# 6_DIG.net
KiCad netlist of a schematic drawn in Altium Designer
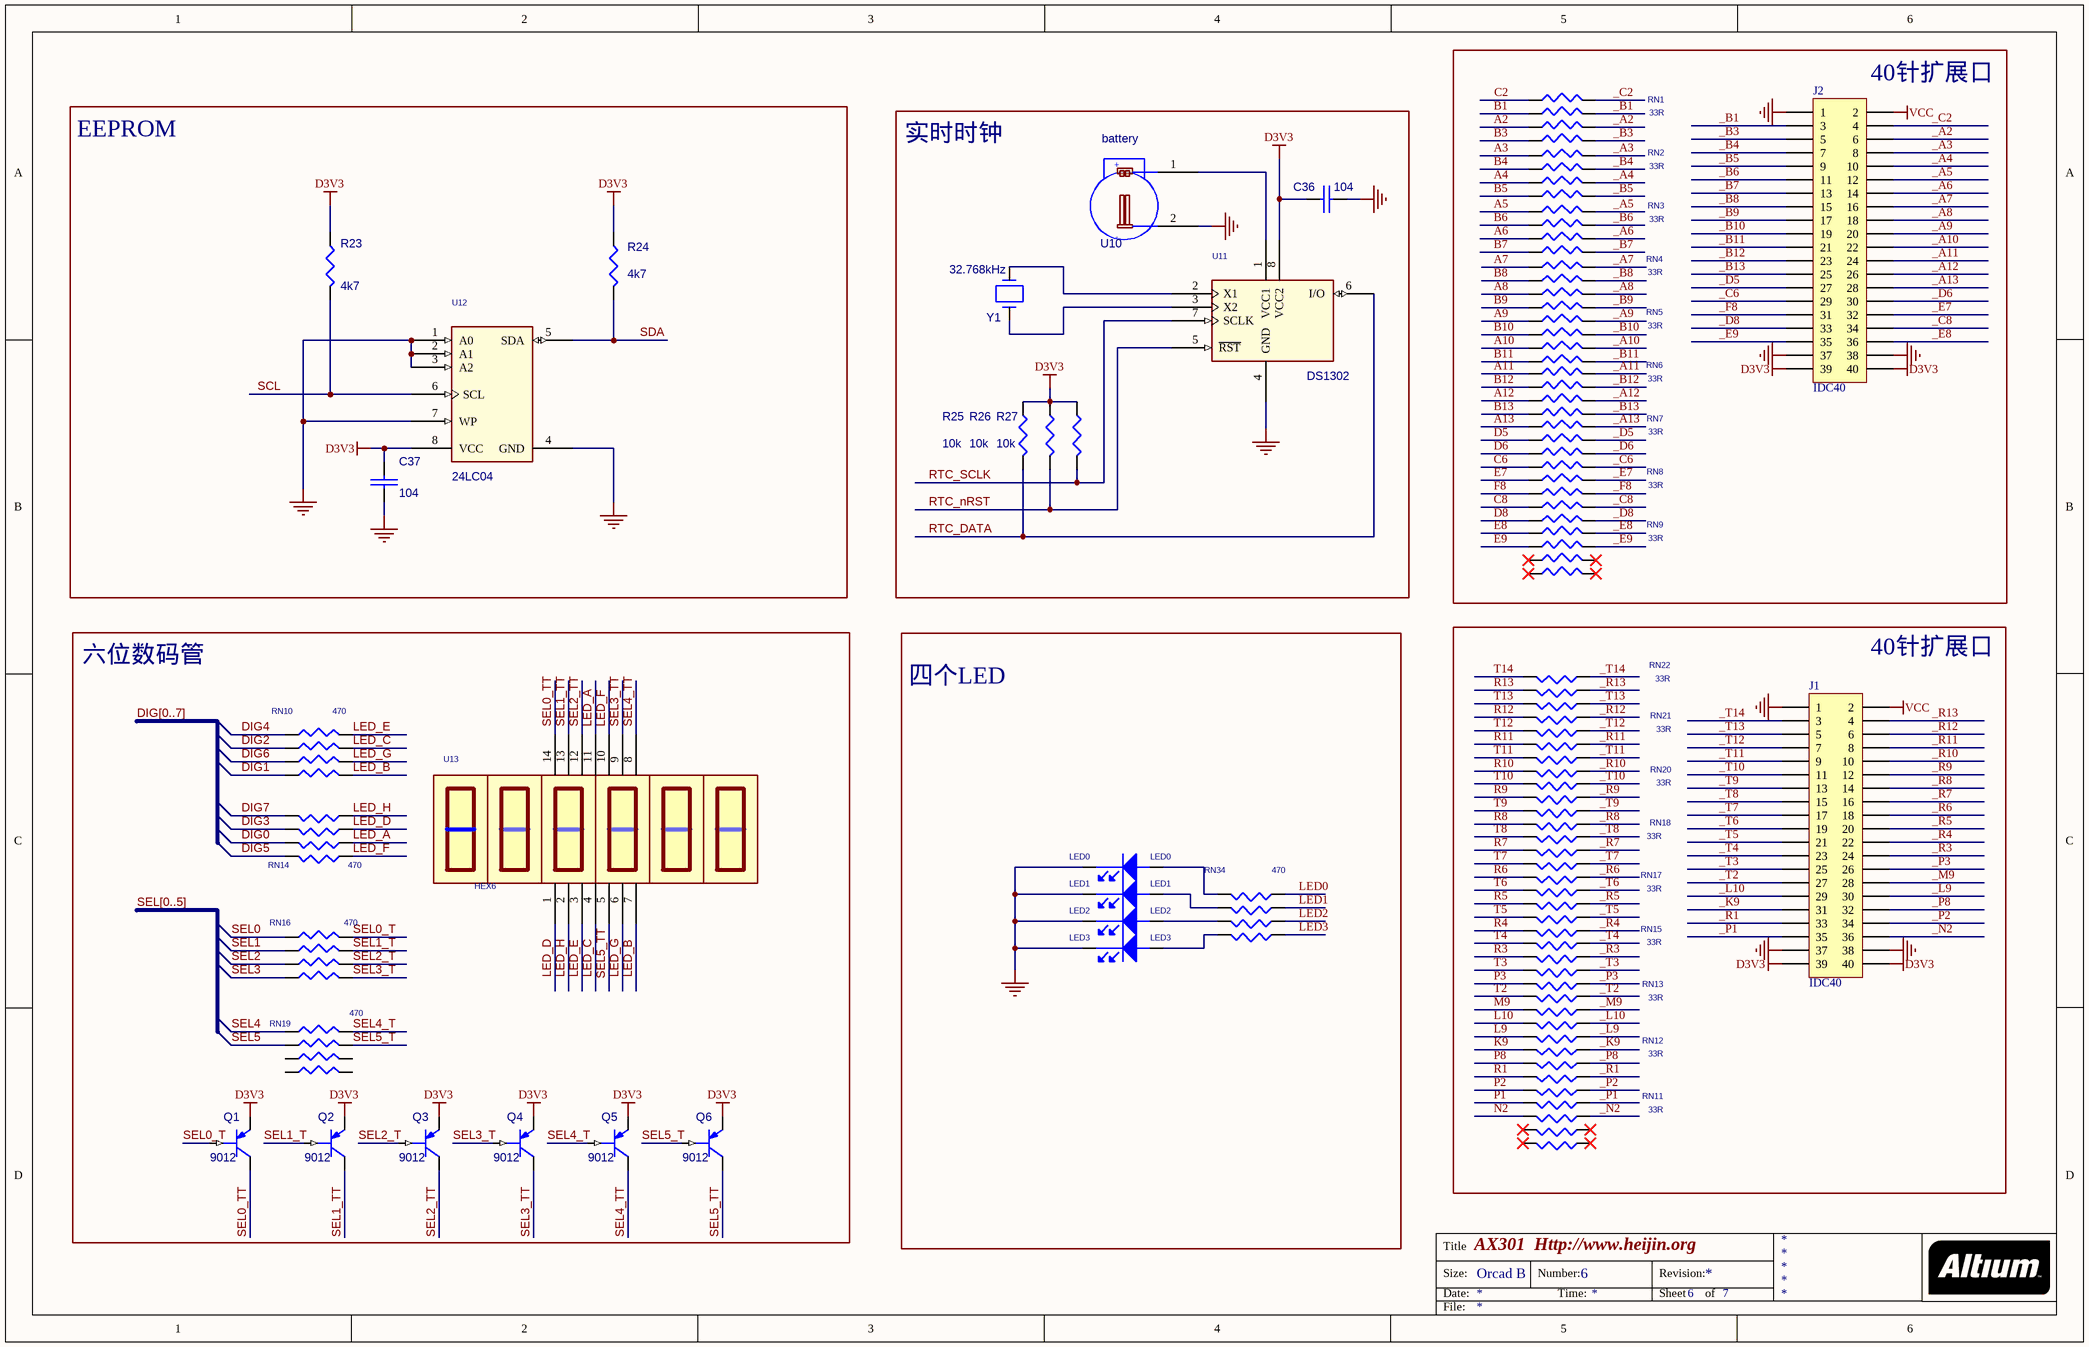
[diagram p0: 6_DIG.SchDoc]

(export (version "E")
  (design (tool "Eeschema 10.0.6"))
  (components
    (comp (ref "C36") (value "104") (footprint "0402") (libsource (lib "*") (part "C_Dup3")))
    (comp (ref "C37") (value "104") (footprint "0402") (libsource (lib "*") (part "C_Dup4")))
    (comp (ref "J1")
      (value "IDC40")
      (footprint "IDC-40J")
      (description "Header, 20-Pin, Dual row")
      (fields (field (name "PUBLISHER") "Altium Limited"))
      (libsource (lib "Miscellaneous Connectors") (part "MHDR2X20"))
    )
    (comp (ref "J2")
      (value "IDC40")
      (footprint "IDC-40J")
      (description "Header, 20-Pin, Dual row")
      (fields (field (name "PUBLISHER") "Altium Limited"))
      (libsource (lib "Miscellaneous Connectors") (part "MHDR2X20"))
    )
    (comp (ref "LED0") (value "LED0") (footprint "LEDSO") (libsource (lib "*") (part "LED_Dup1")))
    (comp (ref "LED1") (value "LED1") (footprint "LEDso") (libsource (lib "*") (part "LED_Dup1")))
    (comp (ref "LED2") (value "LED2") (footprint "LEDSO") (libsource (lib "*") (part "LED_Dup1")))
    (comp (ref "LED3") (value "LED3") (footprint "LEDSO") (libsource (lib "*") (part "LED_Dup1")))
    (comp (ref "Q1") (value "9012") (footprint "SOT23") (libsource (lib "*") (part "PNP")))
    (comp (ref "Q2") (value "9012") (footprint "SOT23") (libsource (lib "*") (part "PNP")))
    (comp (ref "Q3") (value "9012") (footprint "SOT23") (libsource (lib "*") (part "PNP")))
    (comp (ref "Q4") (value "9012") (footprint "SOT23") (libsource (lib "*") (part "PNP")))
    (comp (ref "Q5") (value "9012") (footprint "SOT23") (libsource (lib "*") (part "PNP")))
    (comp (ref "Q6") (value "9012") (footprint "SOT23") (libsource (lib "*") (part "PNP")))
    (comp (ref "R23") (value "4k7") (footprint "0603") (libsource (lib "*") (part "R_Dup6")))
    (comp (ref "R24") (value "4k7") (footprint "0603") (libsource (lib "*") (part "R_Dup6")))
    (comp (ref "R25") (value "10k") (footprint "0603") (libsource (lib "*") (part "R_Dup5")))
    (comp (ref "R26") (value "10k") (footprint "0603") (libsource (lib "*") (part "R_Dup5")))
    (comp (ref "R27") (value "10k") (footprint "0603") (libsource (lib "*") (part "R_Dup5")))
    (comp (ref "RN1") (value "33R") (footprint "RN-8P") (libsource (lib "*") (part "RN_Dup1")))
    (comp (ref "RN2") (value "33R") (footprint "RN-8P") (libsource (lib "*") (part "RN_Dup1")))
    (comp (ref "RN3") (value "33R") (footprint "RN-8P") (libsource (lib "*") (part "RN_Dup1")))
    (comp (ref "RN4") (value "33R") (footprint "RN-8P") (libsource (lib "*") (part "RN_Dup1")))
    (comp (ref "RN5") (value "33R") (footprint "RN-8P") (libsource (lib "*") (part "RN_Dup1")))
    (comp (ref "RN6") (value "33R") (footprint "RN-8P") (libsource (lib "*") (part "RN_Dup1")))
    (comp (ref "RN7") (value "33R") (footprint "RN-8P") (libsource (lib "*") (part "RN_Dup1")))
    (comp (ref "RN8") (value "33R") (footprint "RN-8P") (libsource (lib "*") (part "RN_Dup1")))
    (comp (ref "RN9") (value "33R") (footprint "RN-8P") (libsource (lib "*") (part "RN_Dup1")))
    (comp (ref "RN10") (value "470") (footprint "RN-8P") (libsource (lib "*") (part "RN")))
    (comp (ref "RN11") (value "33R") (footprint "RN-8P") (libsource (lib "*") (part "RN_Dup1")))
    (comp (ref "RN12") (value "33R") (footprint "RN-8P") (libsource (lib "*") (part "RN_Dup1")))
    (comp (ref "RN13") (value "33R") (footprint "RN-8P") (libsource (lib "*") (part "RN_Dup1")))
    (comp (ref "RN14") (value "470") (footprint "RN-8P") (libsource (lib "*") (part "RN")))
    (comp (ref "RN15") (value "33R") (footprint "RN-8P") (libsource (lib "*") (part "RN_Dup1")))
    (comp (ref "RN16") (value "470") (footprint "RN-8P") (libsource (lib "*") (part "RN")))
    (comp (ref "RN17") (value "33R") (footprint "RN-8P") (libsource (lib "*") (part "RN_Dup1")))
    (comp (ref "RN18") (value "33R") (footprint "RN-8P") (libsource (lib "*") (part "RN_Dup1")))
    (comp (ref "RN19") (value "470") (footprint "RN-8P") (libsource (lib "*") (part "RN")))
    (comp (ref "RN20") (value "33R") (footprint "RN-8P") (libsource (lib "*") (part "RN_Dup1")))
    (comp (ref "RN21") (value "33R") (footprint "RN-8P") (libsource (lib "*") (part "RN_Dup1")))
    (comp (ref "RN22") (value "33R") (footprint "RN-8P") (libsource (lib "*") (part "RN_Dup1")))
    (comp (ref "RN34") (value "470") (footprint "RN-8P") (libsource (lib "*") (part "RN")))
    (comp (ref "U10") (value "battery") (footprint "BATSO") (libsource (lib "*") (part "battery")))
    (comp (ref "U11")
      (value "DS1302")
      (fields (field (name "PART NUMBER") "TMP-13") (field (name "ICA_PARTNUM") "$$2098133$$DS1302S"))
      (libsource (lib "*") (part "DS1302_8SO"))
    )
    (comp (ref "U12") (value "24LC04") (libsource (lib "*") (part "24LC04B_0")))
    (comp (ref "U13") (value "HEX6") (libsource (lib "*") (part "HEX6")))
    (comp (ref "Y1") (value "32.768kHz") (libsource (lib "*") (part "ZTA")))
  )
  (nets
    (net (code "1") (name "/A2") (class "Default")
      (node (ref "RN1") (pin "3") (pinfunction "3_3") (pintype "passive"))
    )
    (net (code "2") (name "/A3") (class "Default")
      (node (ref "RN2") (pin "1") (pinfunction "1_1") (pintype "passive"))
    )
    (net (code "3") (name "/A4") (class "Default")
      (node (ref "RN2") (pin "3") (pinfunction "3_3") (pintype "passive"))
    )
    (net (code "4") (name "/A5") (class "Default")
      (node (ref "RN3") (pin "1") (pinfunction "1_1") (pintype "passive"))
    )
    (net (code "5") (name "/A6") (class "Default")
      (node (ref "RN3") (pin "3") (pinfunction "3_3") (pintype "passive"))
    )
    (net (code "6") (name "/A7") (class "Default")
      (node (ref "RN4") (pin "1") (pinfunction "1_1") (pintype "passive"))
    )
    (net (code "7") (name "/A8") (class "Default")
      (node (ref "RN4") (pin "3") (pinfunction "3_3") (pintype "passive"))
    )
    (net (code "8") (name "/A9") (class "Default")
      (node (ref "RN5") (pin "1") (pinfunction "1_1") (pintype "passive"))
    )
    (net (code "9") (name "/A10") (class "Default")
      (node (ref "RN5") (pin "3") (pinfunction "3_3") (pintype "passive"))
    )
    (net (code "10") (name "/A11") (class "Default")
      (node (ref "RN6") (pin "1") (pinfunction "1_1") (pintype "passive"))
    )
    (net (code "11") (name "/A12") (class "Default")
      (node (ref "RN6") (pin "3") (pinfunction "3_3") (pintype "passive"))
    )
    (net (code "12") (name "/A13") (class "Default")
      (node (ref "RN7") (pin "1") (pinfunction "1_1") (pintype "passive"))
    )
    (net (code "13") (name "/B1") (class "Default")
      (node (ref "RN1") (pin "2") (pinfunction "2_2") (pintype "passive"))
    )
    (net (code "14") (name "/B3") (class "Default")
      (node (ref "RN1") (pin "4") (pinfunction "4_4") (pintype "passive"))
    )
    (net (code "15") (name "/B4") (class "Default")
      (node (ref "RN2") (pin "2") (pinfunction "2_2") (pintype "passive"))
    )
    (net (code "16") (name "/B5") (class "Default")
      (node (ref "RN2") (pin "4") (pinfunction "4_4") (pintype "passive"))
    )
    (net (code "17") (name "/B6") (class "Default")
      (node (ref "RN3") (pin "2") (pinfunction "2_2") (pintype "passive"))
    )
    (net (code "18") (name "/B7") (class "Default")
      (node (ref "RN3") (pin "4") (pinfunction "4_4") (pintype "passive"))
    )
    (net (code "19") (name "/B8") (class "Default")
      (node (ref "RN4") (pin "2") (pinfunction "2_2") (pintype "passive"))
    )
    (net (code "20") (name "/B9") (class "Default")
      (node (ref "RN4") (pin "4") (pinfunction "4_4") (pintype "passive"))
    )
    (net (code "21") (name "/B10") (class "Default")
      (node (ref "RN5") (pin "2") (pinfunction "2_2") (pintype "passive"))
    )
    (net (code "22") (name "/B11") (class "Default")
      (node (ref "RN5") (pin "4") (pinfunction "4_4") (pintype "passive"))
    )
    (net (code "23") (name "/B12") (class "Default")
      (node (ref "RN6") (pin "2") (pinfunction "2_2") (pintype "passive"))
    )
    (net (code "24") (name "/B13") (class "Default")
      (node (ref "RN6") (pin "4") (pinfunction "4_4") (pintype "passive"))
    )
    (net (code "25") (name "/C2") (class "Default")
      (node (ref "RN1") (pin "1") (pinfunction "1_1") (pintype "passive"))
    )
    (net (code "26") (name "/C6") (class "Default")
      (node (ref "RN7") (pin "4") (pinfunction "4_4") (pintype "passive"))
    )
    (net (code "27") (name "/C8") (class "Default")
      (node (ref "RN8") (pin "3") (pinfunction "3_3") (pintype "passive"))
    )
    (net (code "28") (name "/D5") (class "Default")
      (node (ref "RN7") (pin "2") (pinfunction "2_2") (pintype "passive"))
    )
    (net (code "29") (name "/D6") (class "Default")
      (node (ref "RN7") (pin "3") (pinfunction "3_3") (pintype "passive"))
    )
    (net (code "30") (name "/D8") (class "Default")
      (node (ref "RN8") (pin "4") (pinfunction "4_4") (pintype "passive"))
    )
    (net (code "31") (name "/DIG0") (class "Default")
      (node (ref "RN14") (pin "7") (pinfunction "7_7") (pintype "passive"))
    )
    (net (code "32") (name "/DIG1") (class "Default")
      (node (ref "RN10") (pin "5") (pinfunction "5_5") (pintype "passive"))
    )
    (net (code "33") (name "/DIG2") (class "Default")
      (node (ref "RN10") (pin "7") (pinfunction "7_7") (pintype "passive"))
    )
    (net (code "34") (name "/DIG3") (class "Default")
      (node (ref "RN14") (pin "6") (pinfunction "6_6") (pintype "passive"))
    )
    (net (code "35") (name "/DIG4") (class "Default")
      (node (ref "RN10") (pin "8") (pinfunction "8_8") (pintype "passive"))
    )
    (net (code "36") (name "/DIG5") (class "Default")
      (node (ref "RN14") (pin "8") (pinfunction "8_8") (pintype "passive"))
    )
    (net (code "37") (name "/DIG6") (class "Default")
      (node (ref "RN10") (pin "6") (pinfunction "6_6") (pintype "passive"))
    )
    (net (code "38") (name "/DIG7") (class "Default")
      (node (ref "RN14") (pin "5") (pinfunction "5_5") (pintype "passive"))
    )
    (net (code "40") (name "/E7") (class "Default")
      (node (ref "RN8") (pin "1") (pinfunction "1_1") (pintype "passive"))
    )
    (net (code "41") (name "/E8") (class "Default")
      (node (ref "RN9") (pin "1") (pinfunction "1_1") (pintype "passive"))
    )
    (net (code "42") (name "/E9") (class "Default")
      (node (ref "RN9") (pin "2") (pinfunction "2_2") (pintype "passive"))
    )
    (net (code "43") (name "/F8") (class "Default")
      (node (ref "RN8") (pin "2") (pinfunction "2_2") (pintype "passive"))
    )
    (net (code "44") (name "/K9") (class "Default")
      (node (ref "RN12") (pin "5") (pinfunction "5_5") (pintype "passive"))
    )
    (net (code "45") (name "/L9") (class "Default")
      (node (ref "RN13") (pin "8") (pinfunction "8_8") (pintype "passive"))
    )
    (net (code "46") (name "/L10") (class "Default")
      (node (ref "RN13") (pin "7") (pinfunction "7_7") (pintype "passive"))
    )
    (net (code "47") (name "/LED0") (class "Default")
      (node (ref "RN34") (pin "4") (pinfunction "4_4") (pintype "passive"))
    )
    (net (code "48") (name "/LED1") (class "Default")
      (node (ref "RN34") (pin "3") (pinfunction "3_3") (pintype "passive"))
    )
    (net (code "49") (name "/LED2") (class "Default")
      (node (ref "RN34") (pin "2") (pinfunction "2_2") (pintype "passive"))
    )
    (net (code "50") (name "/LED3") (class "Default")
      (node (ref "RN34") (pin "1") (pinfunction "1_1") (pintype "passive"))
    )
    (net (code "51") (name "/LED_A") (class "Default")
      (node (ref "RN14") (pin "2") (pinfunction "2_2") (pintype "passive"))
      (node (ref "U13") (pin "11") (pinfunction "11_11") (pintype "passive"))
    )
    (net (code "52") (name "/LED_B") (class "Default")
      (node (ref "RN10") (pin "4") (pinfunction "4_4") (pintype "passive"))
      (node (ref "U13") (pin "7") (pinfunction "7_7") (pintype "passive"))
    )
    (net (code "53") (name "/LED_C") (class "Default")
      (node (ref "RN10") (pin "2") (pinfunction "2_2") (pintype "passive"))
      (node (ref "U13") (pin "4") (pinfunction "4_4") (pintype "passive"))
    )
    (net (code "54") (name "/LED_D") (class "Default")
      (node (ref "RN14") (pin "3") (pinfunction "3_3") (pintype "passive"))
      (node (ref "U13") (pin "1") (pinfunction "1_1") (pintype "passive"))
    )
    (net (code "55") (name "/LED_E") (class "Default")
      (node (ref "RN10") (pin "1") (pinfunction "1_1") (pintype "passive"))
      (node (ref "U13") (pin "3") (pinfunction "3_3") (pintype "passive"))
    )
    (net (code "56") (name "/LED_F") (class "Default")
      (node (ref "RN14") (pin "1") (pinfunction "1_1") (pintype "passive"))
      (node (ref "U13") (pin "10") (pinfunction "10_10") (pintype "passive"))
    )
    (net (code "57") (name "/LED_G") (class "Default")
      (node (ref "RN10") (pin "3") (pinfunction "3_3") (pintype "passive"))
      (node (ref "U13") (pin "6") (pinfunction "6_6") (pintype "passive"))
    )
    (net (code "58") (name "/LED_H") (class "Default")
      (node (ref "RN14") (pin "4") (pinfunction "4_4") (pintype "passive"))
      (node (ref "U13") (pin "2") (pinfunction "2_2") (pintype "passive"))
    )
    (net (code "59") (name "/M9") (class "Default")
      (node (ref "RN13") (pin "6") (pinfunction "6_6") (pintype "passive"))
    )
    (net (code "60") (name "/N2") (class "Default")
      (node (ref "RN11") (pin "6") (pinfunction "6_6") (pintype "passive"))
    )
    (net (code "61") (name "/P1") (class "Default")
      (node (ref "RN11") (pin "5") (pinfunction "5_5") (pintype "passive"))
    )
    (net (code "62") (name "/P2") (class "Default")
      (node (ref "RN12") (pin "8") (pinfunction "8_8") (pintype "passive"))
    )
    (net (code "63") (name "/P3") (class "Default")
      (node (ref "RN15") (pin "8") (pinfunction "8_8") (pintype "passive"))
    )
    (net (code "64") (name "/P8") (class "Default")
      (node (ref "RN12") (pin "6") (pinfunction "6_6") (pintype "passive"))
    )
    (net (code "65") (name "/R1") (class "Default")
      (node (ref "RN12") (pin "7") (pinfunction "7_7") (pintype "passive"))
    )
    (net (code "66") (name "/R3") (class "Default")
      (node (ref "RN15") (pin "6") (pinfunction "6_6") (pintype "passive"))
    )
    (net (code "67") (name "/R4") (class "Default")
      (node (ref "RN17") (pin "8") (pinfunction "8_8") (pintype "passive"))
    )
    (net (code "68") (name "/R5") (class "Default")
      (node (ref "RN17") (pin "6") (pinfunction "6_6") (pintype "passive"))
    )
    (net (code "69") (name "/R6") (class "Default")
      (node (ref "RN18") (pin "8") (pinfunction "8_8") (pintype "passive"))
    )
    (net (code "70") (name "/R7") (class "Default")
      (node (ref "RN18") (pin "6") (pinfunction "6_6") (pintype "passive"))
    )
    (net (code "71") (name "/R8") (class "Default")
      (node (ref "RN20") (pin "8") (pinfunction "8_8") (pintype "passive"))
    )
    (net (code "72") (name "/R9") (class "Default")
      (node (ref "RN20") (pin "6") (pinfunction "6_6") (pintype "passive"))
    )
    (net (code "73") (name "/R10") (class "Default")
      (node (ref "RN21") (pin "8") (pinfunction "8_8") (pintype "passive"))
    )
    (net (code "74") (name "/R11") (class "Default")
      (node (ref "RN21") (pin "6") (pinfunction "6_6") (pintype "passive"))
    )
    (net (code "75") (name "/R12") (class "Default")
      (node (ref "RN22") (pin "8") (pinfunction "8_8") (pintype "passive"))
    )
    (net (code "76") (name "/R13") (class "Default")
      (node (ref "RN22") (pin "6") (pinfunction "6_6") (pintype "passive"))
    )
    (net (code "77") (name "/RTC_DATA") (class "Default")
      (node (ref "R25") (pin "2") (pinfunction "2_2") (pintype "passive"))
      (node (ref "U11") (pin "6") (pinfunction "I/O_6") (pintype "bidirectional"))
    )
    (net (code "78") (name "/RTC_SCLK") (class "Default")
      (node (ref "R27") (pin "2") (pinfunction "2_2") (pintype "passive"))
      (node (ref "U11") (pin "7") (pinfunction "SCLK_7") (pintype "input"))
    )
    (net (code "79") (name "/RTC_nRST") (class "Default")
      (node (ref "R26") (pin "2") (pinfunction "2_2") (pintype "passive"))
      (node (ref "U11") (pin "5") (pinfunction "~{RST}_5") (pintype "input"))
    )
    (net (code "80") (name "/SCL") (class "Default")
      (node (ref "R23") (pin "2") (pinfunction "2_2") (pintype "passive"))
      (node (ref "U12") (pin "6") (pinfunction "SCL_6") (pintype "input"))
    )
    (net (code "81") (name "/SDA") (class "Default")
      (node (ref "R24") (pin "2") (pinfunction "2_2") (pintype "passive"))
      (node (ref "U12") (pin "5") (pinfunction "SDA_5") (pintype "bidirectional"))
    )
    (net (code "82") (name "/SEL0") (class "Default")
      (node (ref "RN16") (pin "8") (pinfunction "8_8") (pintype "passive"))
    )
    (net (code "83") (name "/SEL0_T") (class "Default")
      (node (ref "Q1") (pin "1") (pinfunction "BASE_1") (pintype "input"))
      (node (ref "RN16") (pin "1") (pinfunction "1_1") (pintype "passive"))
    )
    (net (code "84") (name "/SEL0_TT") (class "Default")
      (node (ref "Q1") (pin "3") (pinfunction "COLLECTOR_3") (pintype "passive"))
      (node (ref "U13") (pin "14") (pinfunction "14_14") (pintype "passive"))
    )
    (net (code "85") (name "/SEL1") (class "Default")
      (node (ref "RN16") (pin "7") (pinfunction "7_7") (pintype "passive"))
    )
    (net (code "86") (name "/SEL1_T") (class "Default")
      (node (ref "Q2") (pin "1") (pinfunction "BASE_1") (pintype "input"))
      (node (ref "RN16") (pin "2") (pinfunction "2_2") (pintype "passive"))
    )
    (net (code "87") (name "/SEL1_TT") (class "Default")
      (node (ref "Q2") (pin "3") (pinfunction "COLLECTOR_3") (pintype "passive"))
      (node (ref "U13") (pin "13") (pinfunction "13_13") (pintype "passive"))
    )
    (net (code "88") (name "/SEL2") (class "Default")
      (node (ref "RN16") (pin "6") (pinfunction "6_6") (pintype "passive"))
    )
    (net (code "89") (name "/SEL2_T") (class "Default")
      (node (ref "Q3") (pin "1") (pinfunction "BASE_1") (pintype "input"))
      (node (ref "RN16") (pin "3") (pinfunction "3_3") (pintype "passive"))
    )
    (net (code "90") (name "/SEL2_TT") (class "Default")
      (node (ref "Q3") (pin "3") (pinfunction "COLLECTOR_3") (pintype "passive"))
      (node (ref "U13") (pin "12") (pinfunction "12_12") (pintype "passive"))
    )
    (net (code "91") (name "/SEL3") (class "Default")
      (node (ref "RN16") (pin "5") (pinfunction "5_5") (pintype "passive"))
    )
    (net (code "92") (name "/SEL3_T") (class "Default")
      (node (ref "Q4") (pin "1") (pinfunction "BASE_1") (pintype "input"))
      (node (ref "RN16") (pin "4") (pinfunction "4_4") (pintype "passive"))
    )
    (net (code "93") (name "/SEL3_TT") (class "Default")
      (node (ref "Q4") (pin "3") (pinfunction "COLLECTOR_3") (pintype "passive"))
      (node (ref "U13") (pin "9") (pinfunction "9_9") (pintype "passive"))
    )
    (net (code "94") (name "/SEL4") (class "Default")
      (node (ref "RN19") (pin "8") (pinfunction "8_8") (pintype "passive"))
    )
    (net (code "95") (name "/SEL4_T") (class "Default")
      (node (ref "Q5") (pin "1") (pinfunction "BASE_1") (pintype "input"))
      (node (ref "RN19") (pin "1") (pinfunction "1_1") (pintype "passive"))
    )
    (net (code "96") (name "/SEL4_TT") (class "Default")
      (node (ref "Q5") (pin "3") (pinfunction "COLLECTOR_3") (pintype "passive"))
      (node (ref "U13") (pin "8") (pinfunction "8_8") (pintype "passive"))
    )
    (net (code "97") (name "/SEL5") (class "Default")
      (node (ref "RN19") (pin "7") (pinfunction "7_7") (pintype "passive"))
    )
    (net (code "98") (name "/SEL5_T") (class "Default")
      (node (ref "Q6") (pin "1") (pinfunction "BASE_1") (pintype "input"))
      (node (ref "RN19") (pin "2") (pinfunction "2_2") (pintype "passive"))
    )
    (net (code "99") (name "/SEL5_TT") (class "Default")
      (node (ref "Q6") (pin "3") (pinfunction "COLLECTOR_3") (pintype "passive"))
      (node (ref "U13") (pin "5") (pinfunction "5_5") (pintype "passive"))
    )
    (net (code "101") (name "/T2") (class "Default")
      (node (ref "RN13") (pin "5") (pinfunction "5_5") (pintype "passive"))
    )
    (net (code "102") (name "/T3") (class "Default")
      (node (ref "RN15") (pin "7") (pinfunction "7_7") (pintype "passive"))
    )
    (net (code "103") (name "/T4") (class "Default")
      (node (ref "RN15") (pin "5") (pinfunction "5_5") (pintype "passive"))
    )
    (net (code "104") (name "/T5") (class "Default")
      (node (ref "RN17") (pin "7") (pinfunction "7_7") (pintype "passive"))
    )
    (net (code "105") (name "/T6") (class "Default")
      (node (ref "RN17") (pin "5") (pinfunction "5_5") (pintype "passive"))
    )
    (net (code "106") (name "/T7") (class "Default")
      (node (ref "RN18") (pin "7") (pinfunction "7_7") (pintype "passive"))
    )
    (net (code "107") (name "/T8") (class "Default")
      (node (ref "RN18") (pin "5") (pinfunction "5_5") (pintype "passive"))
    )
    (net (code "108") (name "/T9") (class "Default")
      (node (ref "RN20") (pin "7") (pinfunction "7_7") (pintype "passive"))
    )
    (net (code "109") (name "/T10") (class "Default")
      (node (ref "RN20") (pin "5") (pinfunction "5_5") (pintype "passive"))
    )
    (net (code "110") (name "/T11") (class "Default")
      (node (ref "RN21") (pin "7") (pinfunction "7_7") (pintype "passive"))
    )
    (net (code "111") (name "/T12") (class "Default")
      (node (ref "RN21") (pin "5") (pinfunction "5_5") (pintype "passive"))
    )
    (net (code "112") (name "/T13") (class "Default")
      (node (ref "RN22") (pin "7") (pinfunction "7_7") (pintype "passive"))
    )
    (net (code "113") (name "/T14") (class "Default")
      (node (ref "RN22") (pin "5") (pinfunction "5_5") (pintype "passive"))
    )
    (net (code "114") (name "/_A2") (class "Default")
      (node (ref "J2") (pin "6") (pinfunction "6_6") (pintype "passive"))
      (node (ref "RN1") (pin "6") (pinfunction "6_6") (pintype "passive"))
    )
    (net (code "115") (name "/_A3") (class "Default")
      (node (ref "J2") (pin "8") (pinfunction "8_8") (pintype "passive"))
      (node (ref "RN2") (pin "8") (pinfunction "8_8") (pintype "passive"))
    )
    (net (code "116") (name "/_A4") (class "Default")
      (node (ref "J2") (pin "10") (pinfunction "10_10") (pintype "passive"))
      (node (ref "RN2") (pin "6") (pinfunction "6_6") (pintype "passive"))
    )
    (net (code "117") (name "/_A5") (class "Default")
      (node (ref "J2") (pin "12") (pinfunction "12_12") (pintype "passive"))
      (node (ref "RN3") (pin "8") (pinfunction "8_8") (pintype "passive"))
    )
    (net (code "118") (name "/_A6") (class "Default")
      (node (ref "J2") (pin "14") (pinfunction "14_14") (pintype "passive"))
      (node (ref "RN3") (pin "6") (pinfunction "6_6") (pintype "passive"))
    )
    (net (code "119") (name "/_A7") (class "Default")
      (node (ref "J2") (pin "16") (pinfunction "16_16") (pintype "passive"))
      (node (ref "RN4") (pin "8") (pinfunction "8_8") (pintype "passive"))
    )
    (net (code "120") (name "/_A8") (class "Default")
      (node (ref "J2") (pin "18") (pinfunction "18_18") (pintype "passive"))
      (node (ref "RN4") (pin "6") (pinfunction "6_6") (pintype "passive"))
    )
    (net (code "121") (name "/_A9") (class "Default")
      (node (ref "J2") (pin "20") (pinfunction "20_20") (pintype "passive"))
      (node (ref "RN5") (pin "8") (pinfunction "8_8") (pintype "passive"))
    )
    (net (code "122") (name "/_A10") (class "Default")
      (node (ref "J2") (pin "22") (pinfunction "22_22") (pintype "passive"))
      (node (ref "RN5") (pin "6") (pinfunction "6_6") (pintype "passive"))
    )
    (net (code "123") (name "/_A11") (class "Default")
      (node (ref "J2") (pin "24") (pinfunction "24_24") (pintype "passive"))
      (node (ref "RN6") (pin "8") (pinfunction "8_8") (pintype "passive"))
    )
    (net (code "124") (name "/_A12") (class "Default")
      (node (ref "J2") (pin "26") (pinfunction "26_26") (pintype "passive"))
      (node (ref "RN6") (pin "6") (pinfunction "6_6") (pintype "passive"))
    )
    (net (code "125") (name "/_A13") (class "Default")
      (node (ref "J2") (pin "28") (pinfunction "28_28") (pintype "passive"))
      (node (ref "RN7") (pin "8") (pinfunction "8_8") (pintype "passive"))
    )
    (net (code "126") (name "/_B1") (class "Default")
      (node (ref "J2") (pin "3") (pinfunction "3_3") (pintype "passive"))
      (node (ref "RN1") (pin "7") (pinfunction "7_7") (pintype "passive"))
    )
    (net (code "127") (name "/_B3") (class "Default")
      (node (ref "J2") (pin "5") (pinfunction "5_5") (pintype "passive"))
      (node (ref "RN1") (pin "5") (pinfunction "5_5") (pintype "passive"))
    )
    (net (code "128") (name "/_B4") (class "Default")
      (node (ref "J2") (pin "7") (pinfunction "7_7") (pintype "passive"))
      (node (ref "RN2") (pin "7") (pinfunction "7_7") (pintype "passive"))
    )
    (net (code "129") (name "/_B5") (class "Default")
      (node (ref "J2") (pin "9") (pinfunction "9_9") (pintype "passive"))
      (node (ref "RN2") (pin "5") (pinfunction "5_5") (pintype "passive"))
    )
    (net (code "130") (name "/_B6") (class "Default")
      (node (ref "J2") (pin "11") (pinfunction "11_11") (pintype "passive"))
      (node (ref "RN3") (pin "7") (pinfunction "7_7") (pintype "passive"))
    )
    (net (code "131") (name "/_B7") (class "Default")
      (node (ref "J2") (pin "13") (pinfunction "13_13") (pintype "passive"))
      (node (ref "RN3") (pin "5") (pinfunction "5_5") (pintype "passive"))
    )
    (net (code "132") (name "/_B8") (class "Default")
      (node (ref "J2") (pin "15") (pinfunction "15_15") (pintype "passive"))
      (node (ref "RN4") (pin "7") (pinfunction "7_7") (pintype "passive"))
    )
    (net (code "133") (name "/_B9") (class "Default")
      (node (ref "J2") (pin "17") (pinfunction "17_17") (pintype "passive"))
      (node (ref "RN4") (pin "5") (pinfunction "5_5") (pintype "passive"))
    )
    (net (code "134") (name "/_B10") (class "Default")
      (node (ref "J2") (pin "19") (pinfunction "19_19") (pintype "passive"))
      (node (ref "RN5") (pin "7") (pinfunction "7_7") (pintype "passive"))
    )
    (net (code "135") (name "/_B11") (class "Default")
      (node (ref "J2") (pin "21") (pinfunction "21_21") (pintype "passive"))
      (node (ref "RN5") (pin "5") (pinfunction "5_5") (pintype "passive"))
    )
    (net (code "136") (name "/_B12") (class "Default")
      (node (ref "J2") (pin "23") (pinfunction "23_23") (pintype "passive"))
      (node (ref "RN6") (pin "7") (pinfunction "7_7") (pintype "passive"))
    )
    (net (code "137") (name "/_B13") (class "Default")
      (node (ref "J2") (pin "25") (pinfunction "25_25") (pintype "passive"))
      (node (ref "RN6") (pin "5") (pinfunction "5_5") (pintype "passive"))
    )
    (net (code "138") (name "/_C2") (class "Default")
      (node (ref "J2") (pin "4") (pinfunction "4_4") (pintype "passive"))
      (node (ref "RN1") (pin "8") (pinfunction "8_8") (pintype "passive"))
    )
    (net (code "139") (name "/_C6") (class "Default")
      (node (ref "J2") (pin "29") (pinfunction "29_29") (pintype "passive"))
      (node (ref "RN7") (pin "5") (pinfunction "5_5") (pintype "passive"))
    )
    (net (code "140") (name "/_C8") (class "Default")
      (node (ref "J2") (pin "34") (pinfunction "34_34") (pintype "passive"))
      (node (ref "RN8") (pin "6") (pinfunction "6_6") (pintype "passive"))
    )
    (net (code "141") (name "/_D5") (class "Default")
      (node (ref "J2") (pin "27") (pinfunction "27_27") (pintype "passive"))
      (node (ref "RN7") (pin "7") (pinfunction "7_7") (pintype "passive"))
    )
    (net (code "142") (name "/_D6") (class "Default")
      (node (ref "J2") (pin "30") (pinfunction "30_30") (pintype "passive"))
      (node (ref "RN7") (pin "6") (pinfunction "6_6") (pintype "passive"))
    )
    (net (code "143") (name "/_D8") (class "Default")
      (node (ref "J2") (pin "33") (pinfunction "33_33") (pintype "passive"))
      (node (ref "RN8") (pin "5") (pinfunction "5_5") (pintype "passive"))
    )
    (net (code "144") (name "/_E7") (class "Default")
      (node (ref "J2") (pin "32") (pinfunction "32_32") (pintype "passive"))
      (node (ref "RN8") (pin "8") (pinfunction "8_8") (pintype "passive"))
    )
    (net (code "145") (name "/_E8") (class "Default")
      (node (ref "J2") (pin "36") (pinfunction "36_36") (pintype "passive"))
      (node (ref "RN9") (pin "8") (pinfunction "8_8") (pintype "passive"))
    )
    (net (code "146") (name "/_E9") (class "Default")
      (node (ref "J2") (pin "35") (pinfunction "35_35") (pintype "passive"))
      (node (ref "RN9") (pin "7") (pinfunction "7_7") (pintype "passive"))
    )
    (net (code "147") (name "/_F8") (class "Default")
      (node (ref "J2") (pin "31") (pinfunction "31_31") (pintype "passive"))
      (node (ref "RN8") (pin "7") (pinfunction "7_7") (pintype "passive"))
    )
    (net (code "148") (name "/_K9") (class "Default")
      (node (ref "J1") (pin "31") (pinfunction "31_31") (pintype "passive"))
      (node (ref "RN12") (pin "4") (pinfunction "4_4") (pintype "passive"))
    )
    (net (code "149") (name "/_L9") (class "Default")
      (node (ref "J1") (pin "30") (pinfunction "30_30") (pintype "passive"))
      (node (ref "RN13") (pin "1") (pinfunction "1_1") (pintype "passive"))
    )
    (net (code "150") (name "/_L10") (class "Default")
      (node (ref "J1") (pin "29") (pinfunction "29_29") (pintype "passive"))
      (node (ref "RN13") (pin "2") (pinfunction "2_2") (pintype "passive"))
    )
    (net (code "151") (name "/_M9") (class "Default")
      (node (ref "J1") (pin "28") (pinfunction "28_28") (pintype "passive"))
      (node (ref "RN13") (pin "3") (pinfunction "3_3") (pintype "passive"))
    )
    (net (code "152") (name "/_N2") (class "Default")
      (node (ref "J1") (pin "36") (pinfunction "36_36") (pintype "passive"))
      (node (ref "RN11") (pin "3") (pinfunction "3_3") (pintype "passive"))
    )
    (net (code "153") (name "/_P1") (class "Default")
      (node (ref "J1") (pin "35") (pinfunction "35_35") (pintype "passive"))
      (node (ref "RN11") (pin "4") (pinfunction "4_4") (pintype "passive"))
    )
    (net (code "154") (name "/_P2") (class "Default")
      (node (ref "J1") (pin "34") (pinfunction "34_34") (pintype "passive"))
      (node (ref "RN12") (pin "1") (pinfunction "1_1") (pintype "passive"))
    )
    (net (code "155") (name "/_P3") (class "Default")
      (node (ref "J1") (pin "26") (pinfunction "26_26") (pintype "passive"))
      (node (ref "RN15") (pin "1") (pinfunction "1_1") (pintype "passive"))
    )
    (net (code "156") (name "/_P8") (class "Default")
      (node (ref "J1") (pin "32") (pinfunction "32_32") (pintype "passive"))
      (node (ref "RN12") (pin "3") (pinfunction "3_3") (pintype "passive"))
    )
    (net (code "157") (name "/_R1") (class "Default")
      (node (ref "J1") (pin "33") (pinfunction "33_33") (pintype "passive"))
      (node (ref "RN12") (pin "2") (pinfunction "2_2") (pintype "passive"))
    )
    (net (code "158") (name "/_R3") (class "Default")
      (node (ref "J1") (pin "24") (pinfunction "24_24") (pintype "passive"))
      (node (ref "RN15") (pin "3") (pinfunction "3_3") (pintype "passive"))
    )
    (net (code "159") (name "/_R4") (class "Default")
      (node (ref "J1") (pin "22") (pinfunction "22_22") (pintype "passive"))
      (node (ref "RN17") (pin "1") (pinfunction "1_1") (pintype "passive"))
    )
    (net (code "160") (name "/_R5") (class "Default")
      (node (ref "J1") (pin "20") (pinfunction "20_20") (pintype "passive"))
      (node (ref "RN17") (pin "3") (pinfunction "3_3") (pintype "passive"))
    )
    (net (code "161") (name "/_R6") (class "Default")
      (node (ref "J1") (pin "18") (pinfunction "18_18") (pintype "passive"))
      (node (ref "RN18") (pin "1") (pinfunction "1_1") (pintype "passive"))
    )
    (net (code "162") (name "/_R7") (class "Default")
      (node (ref "J1") (pin "16") (pinfunction "16_16") (pintype "passive"))
      (node (ref "RN18") (pin "3") (pinfunction "3_3") (pintype "passive"))
    )
    (net (code "163") (name "/_R8") (class "Default")
      (node (ref "J1") (pin "14") (pinfunction "14_14") (pintype "passive"))
      (node (ref "RN20") (pin "1") (pinfunction "1_1") (pintype "passive"))
    )
    (net (code "164") (name "/_R9") (class "Default")
      (node (ref "J1") (pin "12") (pinfunction "12_12") (pintype "passive"))
      (node (ref "RN20") (pin "3") (pinfunction "3_3") (pintype "passive"))
    )
    (net (code "165") (name "/_R10") (class "Default")
      (node (ref "J1") (pin "10") (pinfunction "10_10") (pintype "passive"))
      (node (ref "RN21") (pin "1") (pinfunction "1_1") (pintype "passive"))
    )
    (net (code "166") (name "/_R11") (class "Default")
      (node (ref "J1") (pin "8") (pinfunction "8_8") (pintype "passive"))
      (node (ref "RN21") (pin "3") (pinfunction "3_3") (pintype "passive"))
    )
    (net (code "167") (name "/_R12") (class "Default")
      (node (ref "J1") (pin "6") (pinfunction "6_6") (pintype "passive"))
      (node (ref "RN22") (pin "1") (pinfunction "1_1") (pintype "passive"))
    )
    (net (code "168") (name "/_R13") (class "Default")
      (node (ref "J1") (pin "4") (pinfunction "4_4") (pintype "passive"))
      (node (ref "RN22") (pin "3") (pinfunction "3_3") (pintype "passive"))
    )
    (net (code "169") (name "/_T2") (class "Default")
      (node (ref "J1") (pin "27") (pinfunction "27_27") (pintype "passive"))
      (node (ref "RN13") (pin "4") (pinfunction "4_4") (pintype "passive"))
    )
    (net (code "170") (name "/_T3") (class "Default")
      (node (ref "J1") (pin "25") (pinfunction "25_25") (pintype "passive"))
      (node (ref "RN15") (pin "2") (pinfunction "2_2") (pintype "passive"))
    )
    (net (code "171") (name "/_T4") (class "Default")
      (node (ref "J1") (pin "23") (pinfunction "23_23") (pintype "passive"))
      (node (ref "RN15") (pin "4") (pinfunction "4_4") (pintype "passive"))
    )
    (net (code "172") (name "/_T5") (class "Default")
      (node (ref "J1") (pin "21") (pinfunction "21_21") (pintype "passive"))
      (node (ref "RN17") (pin "2") (pinfunction "2_2") (pintype "passive"))
    )
    (net (code "173") (name "/_T6") (class "Default")
      (node (ref "J1") (pin "19") (pinfunction "19_19") (pintype "passive"))
      (node (ref "RN17") (pin "4") (pinfunction "4_4") (pintype "passive"))
    )
    (net (code "174") (name "/_T7") (class "Default")
      (node (ref "J1") (pin "17") (pinfunction "17_17") (pintype "passive"))
      (node (ref "RN18") (pin "2") (pinfunction "2_2") (pintype "passive"))
    )
    (net (code "175") (name "/_T8") (class "Default")
      (node (ref "J1") (pin "15") (pinfunction "15_15") (pintype "passive"))
      (node (ref "RN18") (pin "4") (pinfunction "4_4") (pintype "passive"))
    )
    (net (code "176") (name "/_T9") (class "Default")
      (node (ref "J1") (pin "13") (pinfunction "13_13") (pintype "passive"))
      (node (ref "RN20") (pin "2") (pinfunction "2_2") (pintype "passive"))
    )
    (net (code "177") (name "/_T10") (class "Default")
      (node (ref "J1") (pin "11") (pinfunction "11_11") (pintype "passive"))
      (node (ref "RN20") (pin "4") (pinfunction "4_4") (pintype "passive"))
    )
    (net (code "178") (name "/_T11") (class "Default")
      (node (ref "J1") (pin "9") (pinfunction "9_9") (pintype "passive"))
      (node (ref "RN21") (pin "2") (pinfunction "2_2") (pintype "passive"))
    )
    (net (code "179") (name "/_T12") (class "Default")
      (node (ref "J1") (pin "7") (pinfunction "7_7") (pintype "passive"))
      (node (ref "RN21") (pin "4") (pinfunction "4_4") (pintype "passive"))
    )
    (net (code "180") (name "/_T13") (class "Default")
      (node (ref "J1") (pin "5") (pinfunction "5_5") (pintype "passive"))
      (node (ref "RN22") (pin "2") (pinfunction "2_2") (pintype "passive"))
    )
    (net (code "181") (name "/_T14") (class "Default")
      (node (ref "J1") (pin "3") (pinfunction "3_3") (pintype "passive"))
      (node (ref "RN22") (pin "4") (pinfunction "4_4") (pintype "passive"))
    )
    (net (code "182") (name "D3V3") (class "Default")
      (node (ref "C36") (pin "1") (pinfunction "1_1") (pintype "passive"))
      (node (ref "C37") (pin "1") (pinfunction "1_1") (pintype "passive"))
      (node (ref "J1") (pin "39") (pinfunction "39_39") (pintype "passive"))
      (node (ref "J1") (pin "40") (pinfunction "40_40") (pintype "passive"))
      (node (ref "J2") (pin "39") (pinfunction "39_39") (pintype "passive"))
      (node (ref "J2") (pin "40") (pinfunction "40_40") (pintype "passive"))
      (node (ref "Q1") (pin "2") (pinfunction "EMITTER_2") (pintype "passive"))
      (node (ref "Q2") (pin "2") (pinfunction "EMITTER_2") (pintype "passive"))
      (node (ref "Q3") (pin "2") (pinfunction "EMITTER_2") (pintype "passive"))
      (node (ref "Q4") (pin "2") (pinfunction "EMITTER_2") (pintype "passive"))
      (node (ref "Q5") (pin "2") (pinfunction "EMITTER_2") (pintype "passive"))
      (node (ref "Q6") (pin "2") (pinfunction "EMITTER_2") (pintype "passive"))
      (node (ref "R23") (pin "1") (pinfunction "1_1") (pintype "passive"))
      (node (ref "R24") (pin "1") (pinfunction "1_1") (pintype "passive"))
      (node (ref "R25") (pin "1") (pinfunction "1_1") (pintype "passive"))
      (node (ref "R26") (pin "1") (pinfunction "1_1") (pintype "passive"))
      (node (ref "R27") (pin "1") (pinfunction "1_1") (pintype "passive"))
      (node (ref "U11") (pin "8") (pinfunction "VCC2_8") (pintype "power_in"))
      (node (ref "U12") (pin "8") (pinfunction "VCC_8") (pintype "power_in"))
    )
    (net (code "183") (name "GND") (class "Default")
      (node (ref "C36") (pin "2") (pinfunction "2_2") (pintype "passive"))
      (node (ref "C37") (pin "2") (pinfunction "2_2") (pintype "passive"))
      (node (ref "J1") (pin "1") (pinfunction "1_1") (pintype "passive"))
      (node (ref "J1") (pin "37") (pinfunction "37_37") (pintype "passive"))
      (node (ref "J1") (pin "38") (pinfunction "38_38") (pintype "passive"))
      (node (ref "J2") (pin "1") (pinfunction "1_1") (pintype "passive"))
      (node (ref "J2") (pin "37") (pinfunction "37_37") (pintype "passive"))
      (node (ref "J2") (pin "38") (pinfunction "38_38") (pintype "passive"))
      (node (ref "LED0") (pin "2") (pinfunction "CATHODE_2") (pintype "passive"))
      (node (ref "LED1") (pin "2") (pinfunction "CATHODE_2") (pintype "passive"))
      (node (ref "LED2") (pin "2") (pinfunction "CATHODE_2") (pintype "passive"))
      (node (ref "LED3") (pin "2") (pinfunction "CATHODE_2") (pintype "passive"))
      (node (ref "U10") (pin "2") (pinfunction "GND_2") (pintype "passive"))
      (node (ref "U11") (pin "4") (pinfunction "GND_4") (pintype "power_in"))
      (node (ref "U12") (pin "1") (pinfunction "A0_1") (pintype "input"))
      (node (ref "U12") (pin "2") (pinfunction "A1_2") (pintype "input"))
      (node (ref "U12") (pin "3") (pinfunction "A2_3") (pintype "input"))
      (node (ref "U12") (pin "4") (pinfunction "GND_4") (pintype "power_in"))
      (node (ref "U12") (pin "7") (pinfunction "WP_7") (pintype "input"))
    )
    (net (code "184") (name "Net-(LED0-ANODE)") (class "Default")
      (node (ref "LED0") (pin "1") (pinfunction "ANODE_1") (pintype "passive"))
      (node (ref "RN34") (pin "5") (pinfunction "5_5") (pintype "passive"))
    )
    (net (code "185") (name "Net-(LED1-ANODE)") (class "Default")
      (node (ref "LED1") (pin "1") (pinfunction "ANODE_1") (pintype "passive"))
      (node (ref "RN34") (pin "6") (pinfunction "6_6") (pintype "passive"))
    )
    (net (code "186") (name "Net-(LED2-ANODE)") (class "Default")
      (node (ref "LED2") (pin "1") (pinfunction "ANODE_1") (pintype "passive"))
      (node (ref "RN34") (pin "7") (pinfunction "7_7") (pintype "passive"))
    )
    (net (code "187") (name "Net-(LED3-ANODE)") (class "Default")
      (node (ref "LED3") (pin "1") (pinfunction "ANODE_1") (pintype "passive"))
      (node (ref "RN34") (pin "8") (pinfunction "8_8") (pintype "passive"))
    )
    (net (code "188") (name "Net-(U10-VBAT)") (class "Default")
      (node (ref "U10") (pin "1") (pinfunction "VBAT_1") (pintype "passive"))
      (node (ref "U11") (pin "1") (pinfunction "VCC1_1") (pintype "power_in"))
    )
    (net (code "189") (name "Net-(U11-X1)") (class "Default")
      (node (ref "U11") (pin "2") (pinfunction "X1_2") (pintype "passive"))
      (node (ref "Y1") (pin "1") (pinfunction "1_1") (pintype "passive"))
    )
    (net (code "190") (name "Net-(U11-X2)") (class "Default")
      (node (ref "U11") (pin "3") (pinfunction "X2_3") (pintype "passive"))
      (node (ref "Y1") (pin "2") (pinfunction "2_2") (pintype "passive"))
    )
    (net (code "191") (name "VCC") (class "Default")
      (node (ref "J1") (pin "2") (pinfunction "2_2") (pintype "passive"))
      (node (ref "J2") (pin "2") (pinfunction "2_2") (pintype "passive"))
    )
    (net (code "192") (name "unconnected-(RN9-Pad3)") (class "Default")
      (node (ref "RN9") (pin "3") (pinfunction "3_3") (pintype "passive+no_connect"))
    )
    (net (code "193") (name "unconnected-(RN9-Pad4)") (class "Default")
      (node (ref "RN9") (pin "4") (pinfunction "4_4") (pintype "passive+no_connect"))
    )
    (net (code "194") (name "unconnected-(RN9-Pad5)") (class "Default")
      (node (ref "RN9") (pin "5") (pinfunction "5_5") (pintype "passive+no_connect"))
    )
    (net (code "195") (name "unconnected-(RN9-Pad6)") (class "Default")
      (node (ref "RN9") (pin "6") (pinfunction "6_6") (pintype "passive+no_connect"))
    )
    (net (code "196") (name "unconnected-(RN11-Pad1)") (class "Default")
      (node (ref "RN11") (pin "1") (pinfunction "1_1") (pintype "passive+no_connect"))
    )
    (net (code "197") (name "unconnected-(RN11-Pad2)") (class "Default")
      (node (ref "RN11") (pin "2") (pinfunction "2_2") (pintype "passive+no_connect"))
    )
    (net (code "198") (name "unconnected-(RN11-Pad7)") (class "Default")
      (node (ref "RN11") (pin "7") (pinfunction "7_7") (pintype "passive+no_connect"))
    )
    (net (code "199") (name "unconnected-(RN11-Pad8)") (class "Default")
      (node (ref "RN11") (pin "8") (pinfunction "8_8") (pintype "passive+no_connect"))
    )
    (net (code "200") (name "unconnected-(RN19-Pad3)") (class "Default")
      (node (ref "RN19") (pin "3") (pinfunction "3_3") (pintype "passive"))
    )
    (net (code "201") (name "unconnected-(RN19-Pad4)") (class "Default")
      (node (ref "RN19") (pin "4") (pinfunction "4_4") (pintype "passive"))
    )
    (net (code "202") (name "unconnected-(RN19-Pad5)") (class "Default")
      (node (ref "RN19") (pin "5") (pinfunction "5_5") (pintype "passive"))
    )
    (net (code "203") (name "unconnected-(RN19-Pad6)") (class "Default")
      (node (ref "RN19") (pin "6") (pinfunction "6_6") (pintype "passive"))
    )
  )
)
